# main.net
KiCad netlist of a schematic drawn in EAGLE
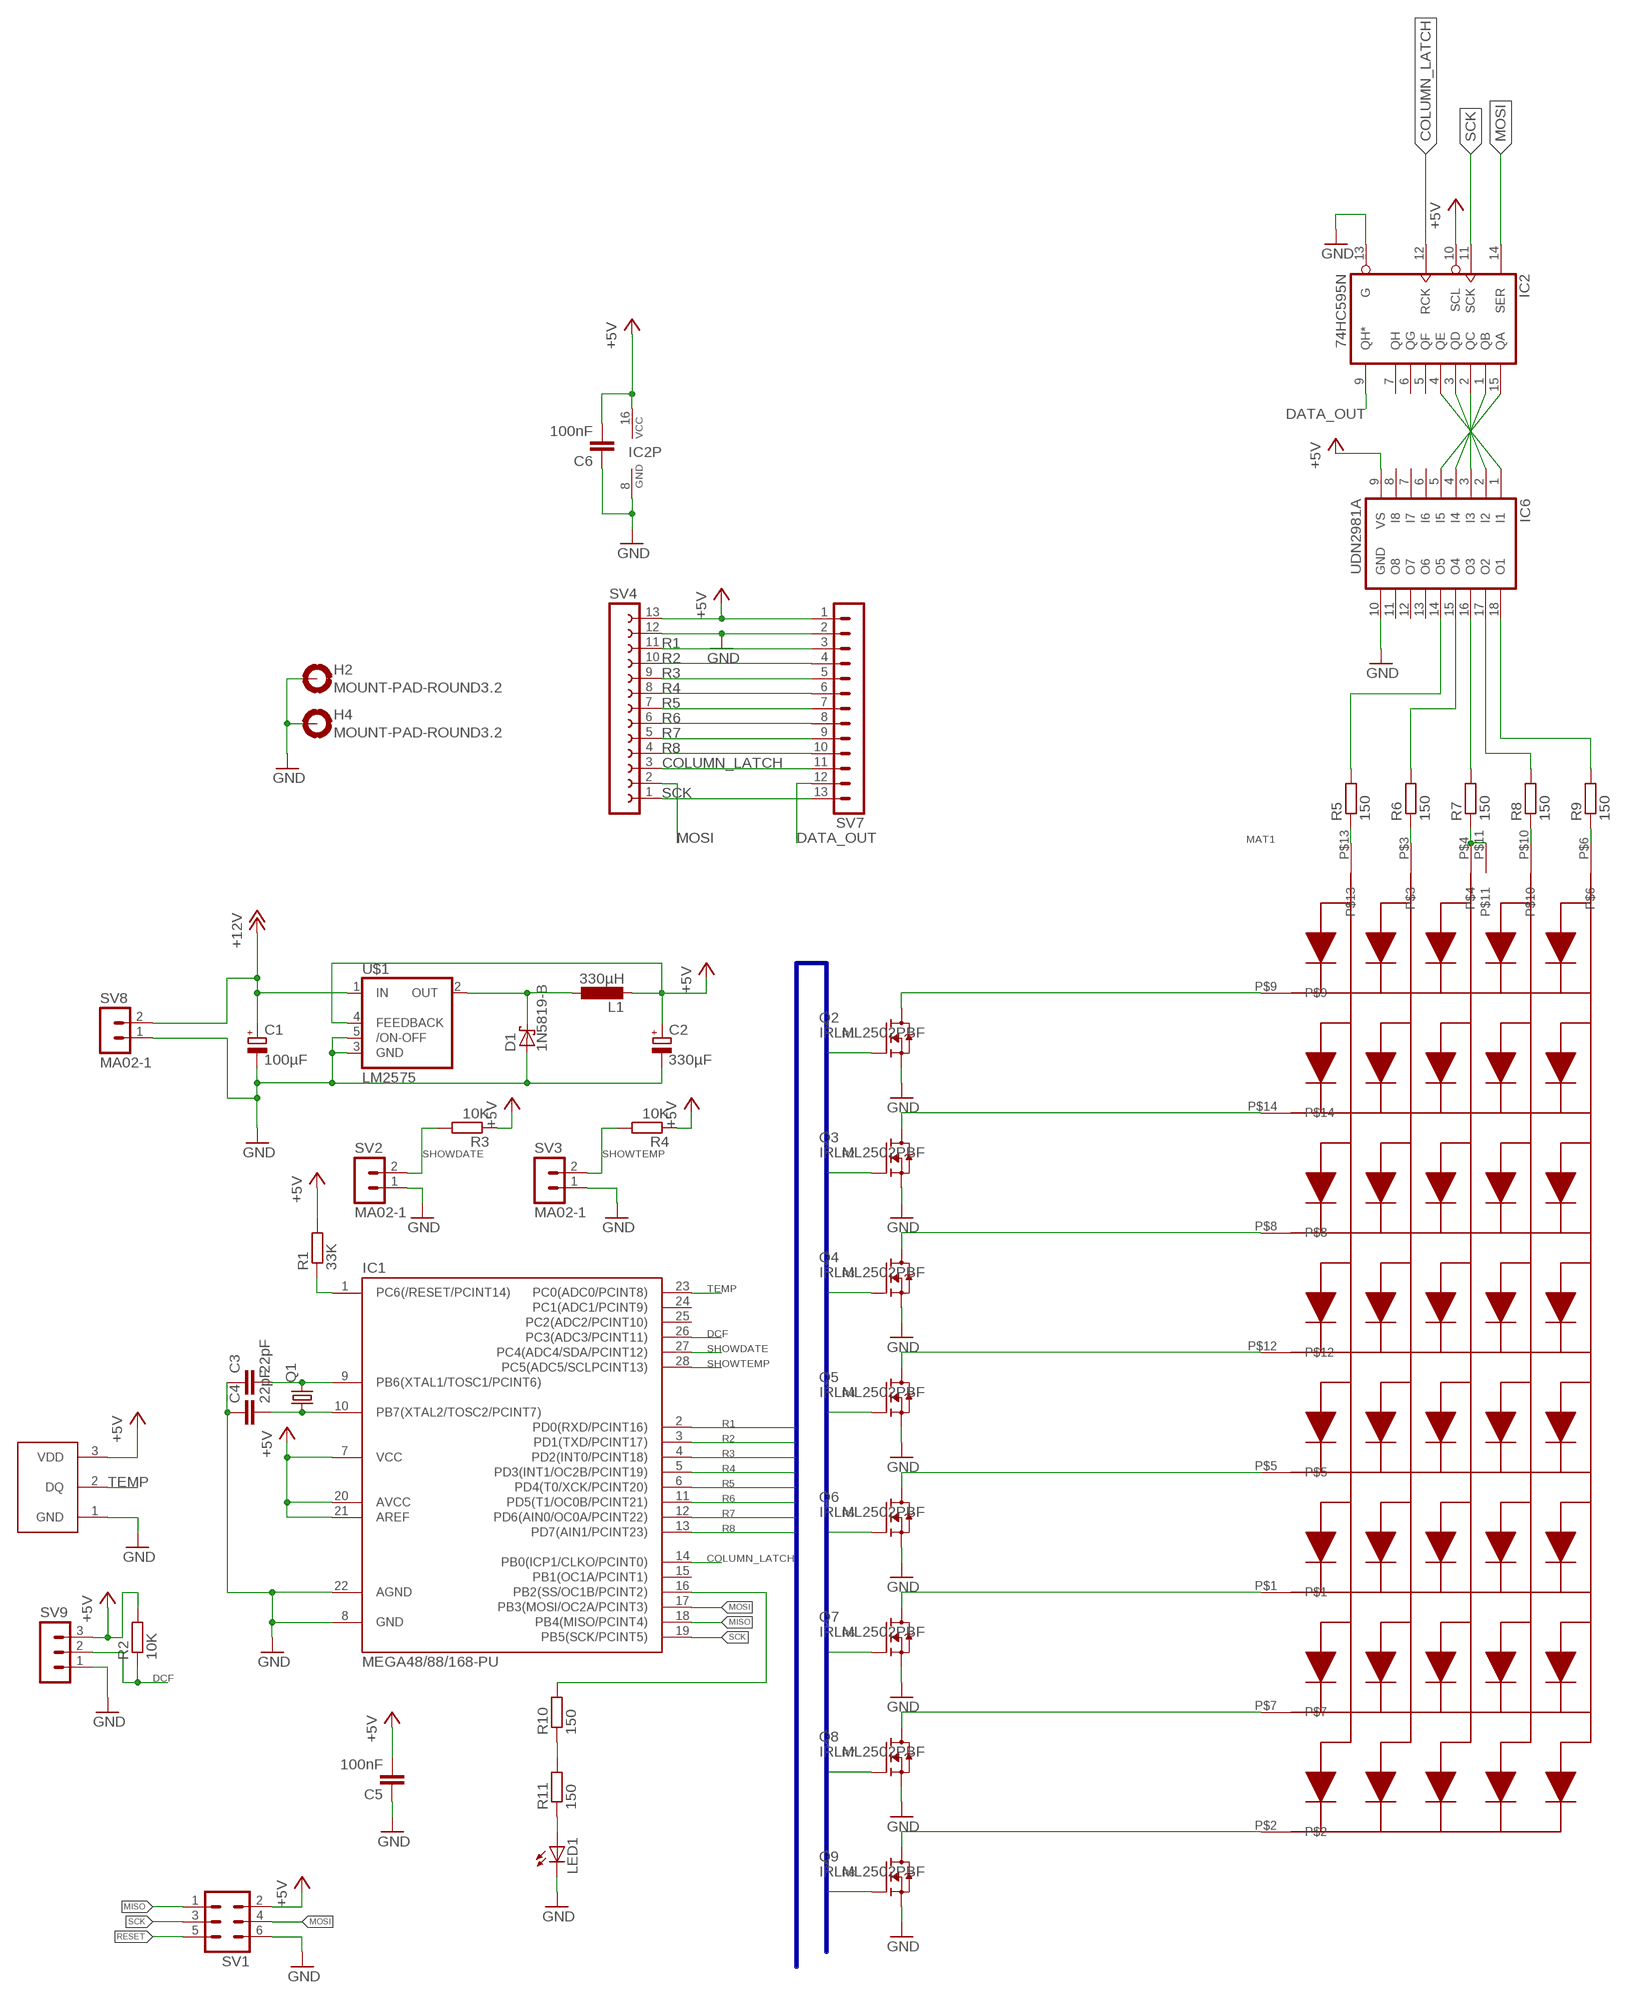
[diagram p0: schematic, sheet 1]

(export (version "E")
  (design (tool "Eeschema 10.0.6"))
  (components
    (comp (ref "C1")
      (value "100µF")
      (footprint "eagle-import:E2,5-5")
      (libsource (lib "eagle-import") (part "CPOL-EUE2.5-5"))
    )
    (comp (ref "C2")
      (value "330µF")
      (footprint "eagle-import:E3,5-8")
      (libsource (lib "eagle-import") (part "CPOL-EUE3.5-8"))
    )
    (comp (ref "C3")
      (value "22pF")
      (footprint "eagle-import:C025-025X050")
      (libsource (lib "eagle-import") (part "C-EU025-025X050"))
    )
    (comp (ref "C4")
      (value "22pF")
      (footprint "eagle-import:C025-025X050")
      (libsource (lib "eagle-import") (part "C-EU025-025X050"))
    )
    (comp (ref "C5")
      (value "100nF")
      (footprint "eagle-import:C0805")
      (libsource (lib "eagle-import") (part "C-EUC0805"))
    )
    (comp (ref "C6")
      (value "100nF")
      (footprint "eagle-import:C0805")
      (libsource (lib "eagle-import") (part "C-EUC0805"))
    )
    (comp (ref "D1")
      (value "1N5819-B")
      (footprint "eagle-import:DO41-7.6")
      (libsource (lib "eagle-import") (part "1N5819-B"))
    )
    (comp (ref "H2")
      (value "MOUNT-PAD-ROUND3.2")
      (footprint "eagle-import:3,2-PAD")
      (libsource (lib "eagle-import") (part "MOUNT-PAD-ROUND3.2"))
    )
    (comp (ref "H4")
      (value "MOUNT-PAD-ROUND3.2")
      (footprint "eagle-import:3,2-PAD")
      (libsource (lib "eagle-import") (part "MOUNT-PAD-ROUND3.2"))
    )
    (comp (ref "IC1")
      (value "MEGA48/88/168-PU")
      (footprint "eagle-import:DIL28-3")
      (libsource (lib "eagle-import") (part "MEGA48/88/168-PU"))
    )
    (comp (ref "IC2")
      (value "74HC595N")
      (footprint "eagle-import:DIL16")
      (libsource (lib "eagle-import") (part "74595NHC"))
    )
    (comp (ref "IC6")
      (value "UDN2981A")
      (footprint "eagle-import:DIL18")
      (libsource (lib "eagle-import") (part "UDN298A1"))
    )
    (comp (ref "L1")
      (value "330µH")
      (footprint "eagle-import:0204V")
      (libsource (lib "eagle-import") (part "L-EU0204V"))
    )
    (comp (ref "LED1")
      (value "LEDSML1206")
      (footprint "eagle-import:SML1206")
      (libsource (lib "eagle-import") (part "LEDSML1206"))
    )
    (comp (ref "MAT1")
      (value "5X8")
      (footprint "eagle-import:5X8")
      (libsource (lib "eagle-import") (part "5X8"))
    )
    (comp (ref "Q1")
      (value "CRYSTALHC49S")
      (footprint "eagle-import:HC49_S")
      (libsource (lib "eagle-import") (part "CRYSTALHC49S"))
    )
    (comp (ref "Q2")
      (value "IRLML2502PBF")
      (footprint "eagle-import:SOT23")
      (libsource (lib "eagle-import") (part "IRLML2502PBF"))
    )
    (comp (ref "Q3")
      (value "IRLML2502PBF")
      (footprint "eagle-import:SOT23")
      (libsource (lib "eagle-import") (part "IRLML2502PBF"))
    )
    (comp (ref "Q4")
      (value "IRLML2502PBF")
      (footprint "eagle-import:SOT23")
      (libsource (lib "eagle-import") (part "IRLML2502PBF"))
    )
    (comp (ref "Q5")
      (value "IRLML2502PBF")
      (footprint "eagle-import:SOT23")
      (libsource (lib "eagle-import") (part "IRLML2502PBF"))
    )
    (comp (ref "Q6")
      (value "IRLML2502PBF")
      (footprint "eagle-import:SOT23")
      (libsource (lib "eagle-import") (part "IRLML2502PBF"))
    )
    (comp (ref "Q7")
      (value "IRLML2502PBF")
      (footprint "eagle-import:SOT23")
      (libsource (lib "eagle-import") (part "IRLML2502PBF"))
    )
    (comp (ref "Q8")
      (value "IRLML2502PBF")
      (footprint "eagle-import:SOT23")
      (libsource (lib "eagle-import") (part "IRLML2502PBF"))
    )
    (comp (ref "Q9")
      (value "IRLML2502PBF")
      (footprint "eagle-import:SOT23")
      (libsource (lib "eagle-import") (part "IRLML2502PBF"))
    )
    (comp (ref "R1")
      (value "33K")
      (footprint "eagle-import:R0805")
      (libsource (lib "eagle-import") (part "R-EU_R0805"))
    )
    (comp (ref "R2")
      (value "10K")
      (footprint "eagle-import:R0805")
      (libsource (lib "eagle-import") (part "R-EU_R0805"))
    )
    (comp (ref "R3")
      (value "10K")
      (footprint "eagle-import:R0805")
      (libsource (lib "eagle-import") (part "R-EU_R0805"))
    )
    (comp (ref "R4")
      (value "10K")
      (footprint "eagle-import:R0805")
      (libsource (lib "eagle-import") (part "R-EU_R0805"))
    )
    (comp (ref "R5")
      (value "150")
      (footprint "eagle-import:R0805")
      (libsource (lib "eagle-import") (part "R-EU_R0805"))
    )
    (comp (ref "R6")
      (value "150")
      (footprint "eagle-import:R0805")
      (libsource (lib "eagle-import") (part "R-EU_R0805"))
    )
    (comp (ref "R7")
      (value "150")
      (footprint "eagle-import:R0805")
      (libsource (lib "eagle-import") (part "R-EU_R0805"))
    )
    (comp (ref "R8")
      (value "150")
      (footprint "eagle-import:R0805")
      (libsource (lib "eagle-import") (part "R-EU_R0805"))
    )
    (comp (ref "R9")
      (value "150")
      (footprint "eagle-import:R0805")
      (libsource (lib "eagle-import") (part "R-EU_R0805"))
    )
    (comp (ref "R10")
      (value "150")
      (footprint "eagle-import:R0805")
      (libsource (lib "eagle-import") (part "R-EU_R0805"))
    )
    (comp (ref "R11")
      (value "150")
      (footprint "eagle-import:R0805")
      (libsource (lib "eagle-import") (part "R-EU_R0805"))
    )
    (comp (ref "SV1")
      (value "MA03-2")
      (footprint "eagle-import:MA03-2")
      (libsource (lib "eagle-import") (part "MA03-2"))
    )
    (comp (ref "SV2")
      (value "MA02-1")
      (footprint "eagle-import:MA02-1")
      (libsource (lib "eagle-import") (part "MA02-1"))
    )
    (comp (ref "SV3")
      (value "MA02-1")
      (footprint "eagle-import:MA02-1")
      (libsource (lib "eagle-import") (part "MA02-1"))
    )
    (comp (ref "SV4")
      (value "FE13W")
      (footprint "eagle-import:FE13W")
      (libsource (lib "eagle-import") (part "FE13W"))
    )
    (comp (ref "SV7")
      (value "MA13-1W")
      (footprint "eagle-import:MA13-1W")
      (fields (field (name "OC_FARNELL") "unknown") (field (name "OC_NEWARK") "unknown"))
      (libsource (lib "eagle-import") (part "MA13-1W"))
    )
    (comp (ref "SV8")
      (value "MA02-1")
      (footprint "eagle-import:MA02-1")
      (libsource (lib "eagle-import") (part "MA02-1"))
    )
    (comp (ref "SV9")
      (value "MA03-1")
      (footprint "eagle-import:MA03-1")
      (libsource (lib "eagle-import") (part "MA03-1"))
    )
    (comp (ref "U$1")
      (value "LM2575")
      (footprint "eagle-import:LM2575")
      (libsource (lib "eagle-import") (part "LM2575"))
    )
    (comp (ref "U$2")
      (value "DS18B20")
      (footprint "eagle-import:TO92")
      (libsource (lib "eagle-import") (part "DS18B20"))
    )
  )
  (nets
    (net (code "1") (name "+5V") (class "Default")
      (node (ref "C2") (pin "+") (pinfunction "+_+") (pintype "passive"))
      (node (ref "C5") (pin "2") (pinfunction "2_2") (pintype "passive"))
      (node (ref "C6") (pin "2") (pinfunction "2_2") (pintype "passive"))
      (node (ref "IC1") (pin "20") (pinfunction "AVCC_20") (pintype "passive"))
      (node (ref "IC1") (pin "21") (pinfunction "AREF_21") (pintype "passive"))
      (node (ref "IC1") (pin "7") (pinfunction "VCC_7") (pintype "power_in"))
      (node (ref "IC2") (pin "10") (pinfunction "SCL_10") (pintype "input"))
      (node (ref "IC2") (pin "16") (pinfunction "VCC_16") (pintype "power_in"))
      (node (ref "IC6") (pin "9") (pinfunction "VS_9") (pintype "passive"))
      (node (ref "L1") (pin "2") (pinfunction "2_2") (pintype "passive"))
      (node (ref "R1") (pin "2") (pinfunction "2_2") (pintype "passive"))
      (node (ref "R2") (pin "2") (pinfunction "2_2") (pintype "passive"))
      (node (ref "R3") (pin "1") (pinfunction "1_1") (pintype "passive"))
      (node (ref "R4") (pin "1") (pinfunction "1_1") (pintype "passive"))
      (node (ref "SV1") (pin "2") (pinfunction "2_2") (pintype "passive"))
      (node (ref "SV4") (pin "13") (pinfunction "13_13") (pintype "passive"))
      (node (ref "SV7") (pin "1") (pinfunction "1_1") (pintype "passive"))
      (node (ref "SV9") (pin "3") (pinfunction "3_3") (pintype "passive"))
      (node (ref "U$1") (pin "4") (pinfunction "FEEDBACK_4") (pintype "input"))
      (node (ref "U$2") (pin "3") (pinfunction "VDD_3") (pintype "bidirectional"))
    )
    (net (code "2") (name "+12V") (class "Default")
      (node (ref "C1") (pin "+") (pinfunction "+_+") (pintype "passive"))
      (node (ref "SV8") (pin "2") (pinfunction "2_2") (pintype "passive"))
      (node (ref "U$1") (pin "1") (pinfunction "IN_1") (pintype "input"))
    )
    (net (code "3") (name "/DATA_OUT") (class "Default")
      (node (ref "IC2") (pin "9") (pinfunction "QH*_9") (pintype "tri_state"))
      (node (ref "SV7") (pin "12") (pinfunction "12_12") (pintype "passive"))
    )
    (net (code "4") (name "/DCF") (class "Default")
      (node (ref "IC1") (pin "26") (pinfunction "PC3(ADC3/PCINT11)_26") (pintype "bidirectional"))
      (node (ref "R2") (pin "1") (pinfunction "1_1") (pintype "passive"))
      (node (ref "SV9") (pin "2") (pinfunction "2_2") (pintype "passive"))
    )
    (net (code "5") (name "/R1") (class "Default")
      (node (ref "IC1") (pin "2") (pinfunction "PD0(RXD/PCINT16)_2") (pintype "bidirectional"))
      (node (ref "Q2") (pin "1") (pinfunction "G_1") (pintype "passive"))
      (node (ref "SV4") (pin "11") (pinfunction "11_11") (pintype "passive"))
      (node (ref "SV7") (pin "3") (pinfunction "3_3") (pintype "passive"))
    )
    (net (code "6") (name "/R2") (class "Default")
      (node (ref "IC1") (pin "3") (pinfunction "PD1(TXD/PCINT17)_3") (pintype "bidirectional"))
      (node (ref "Q3") (pin "1") (pinfunction "G_1") (pintype "passive"))
      (node (ref "SV4") (pin "10") (pinfunction "10_10") (pintype "passive"))
      (node (ref "SV7") (pin "4") (pinfunction "4_4") (pintype "passive"))
    )
    (net (code "7") (name "/R3") (class "Default")
      (node (ref "IC1") (pin "4") (pinfunction "PD2(INT0/PCINT18)_4") (pintype "bidirectional"))
      (node (ref "Q4") (pin "1") (pinfunction "G_1") (pintype "passive"))
      (node (ref "SV4") (pin "9") (pinfunction "9_9") (pintype "passive"))
      (node (ref "SV7") (pin "5") (pinfunction "5_5") (pintype "passive"))
    )
    (net (code "8") (name "/R4") (class "Default")
      (node (ref "IC1") (pin "5") (pinfunction "PD3(INT1/OC2B/PCINT19)_5") (pintype "bidirectional"))
      (node (ref "Q5") (pin "1") (pinfunction "G_1") (pintype "passive"))
      (node (ref "SV4") (pin "8") (pinfunction "8_8") (pintype "passive"))
      (node (ref "SV7") (pin "6") (pinfunction "6_6") (pintype "passive"))
    )
    (net (code "9") (name "/R5") (class "Default")
      (node (ref "IC1") (pin "6") (pinfunction "PD4(T0/XCK/PCINT20)_6") (pintype "bidirectional"))
      (node (ref "Q6") (pin "1") (pinfunction "G_1") (pintype "passive"))
      (node (ref "SV4") (pin "7") (pinfunction "7_7") (pintype "passive"))
      (node (ref "SV7") (pin "7") (pinfunction "7_7") (pintype "passive"))
    )
    (net (code "10") (name "/R6") (class "Default")
      (node (ref "IC1") (pin "11") (pinfunction "PD5(T1/OC0B/PCINT21)_11") (pintype "bidirectional"))
      (node (ref "Q7") (pin "1") (pinfunction "G_1") (pintype "passive"))
      (node (ref "SV4") (pin "6") (pinfunction "6_6") (pintype "passive"))
      (node (ref "SV7") (pin "8") (pinfunction "8_8") (pintype "passive"))
    )
    (net (code "11") (name "/R7") (class "Default")
      (node (ref "IC1") (pin "12") (pinfunction "PD6(AIN0/OC0A/PCINT22)_12") (pintype "bidirectional"))
      (node (ref "Q8") (pin "1") (pinfunction "G_1") (pintype "passive"))
      (node (ref "SV4") (pin "5") (pinfunction "5_5") (pintype "passive"))
      (node (ref "SV7") (pin "9") (pinfunction "9_9") (pintype "passive"))
    )
    (net (code "12") (name "/R8") (class "Default")
      (node (ref "IC1") (pin "13") (pinfunction "PD7(AIN1/PCINT23)_13") (pintype "bidirectional"))
      (node (ref "Q9") (pin "1") (pinfunction "G_1") (pintype "passive"))
      (node (ref "SV4") (pin "4") (pinfunction "4_4") (pintype "passive"))
      (node (ref "SV7") (pin "10") (pinfunction "10_10") (pintype "passive"))
    )
    (net (code "13") (name "/SHOWDATE") (class "Default")
      (node (ref "IC1") (pin "27") (pinfunction "PC4(ADC4/SDA/PCINT12)_27") (pintype "bidirectional"))
      (node (ref "R3") (pin "2") (pinfunction "2_2") (pintype "passive"))
      (node (ref "SV2") (pin "2") (pinfunction "2_2") (pintype "passive"))
    )
    (net (code "14") (name "/SHOWTEMP") (class "Default")
      (node (ref "IC1") (pin "28") (pinfunction "PC5(ADC5/SCLPCINT13)_28") (pintype "bidirectional"))
      (node (ref "R4") (pin "2") (pinfunction "2_2") (pintype "passive"))
      (node (ref "SV3") (pin "2") (pinfunction "2_2") (pintype "passive"))
    )
    (net (code "15") (name "/TEMP") (class "Default")
      (node (ref "IC1") (pin "23") (pinfunction "PC0(ADC0/PCINT8)_23") (pintype "bidirectional"))
      (node (ref "U$2") (pin "2") (pinfunction "DQ_2") (pintype "bidirectional"))
    )
    (net (code "16") (name "COLUMN_LATCH") (class "Default")
      (node (ref "IC1") (pin "14") (pinfunction "PB0(ICP1/CLKO/PCINT0)_14") (pintype "bidirectional"))
      (node (ref "IC2") (pin "12") (pinfunction "RCK_12") (pintype "input"))
      (node (ref "SV4") (pin "3") (pinfunction "3_3") (pintype "passive"))
      (node (ref "SV7") (pin "11") (pinfunction "11_11") (pintype "passive"))
    )
    (net (code "17") (name "GND") (class "Default")
      (node (ref "C1") (pin "-") (pinfunction "-_-") (pintype "passive"))
      (node (ref "C2") (pin "-") (pinfunction "-_-") (pintype "passive"))
      (node (ref "C3") (pin "1") (pinfunction "1_1") (pintype "passive"))
      (node (ref "C4") (pin "1") (pinfunction "1_1") (pintype "passive"))
      (node (ref "C5") (pin "1") (pinfunction "1_1") (pintype "passive"))
      (node (ref "C6") (pin "1") (pinfunction "1_1") (pintype "passive"))
      (node (ref "D1") (pin "A") (pinfunction "A_A") (pintype "passive"))
      (node (ref "H2") (pin "B3,2") (pinfunction "MOUNT_B3,2") (pintype "passive"))
      (node (ref "H4") (pin "B3,2") (pinfunction "MOUNT_B3,2") (pintype "passive"))
      (node (ref "IC1") (pin "22") (pinfunction "AGND_22") (pintype "power_in"))
      (node (ref "IC1") (pin "8") (pinfunction "GND_8") (pintype "power_in"))
      (node (ref "IC2") (pin "13") (pinfunction "G_13") (pintype "input"))
      (node (ref "IC2") (pin "8") (pinfunction "GND_8") (pintype "power_in"))
      (node (ref "IC6") (pin "10") (pinfunction "GND_10") (pintype "power_in"))
      (node (ref "LED1") (pin "C") (pinfunction "C_C") (pintype "passive"))
      (node (ref "Q2") (pin "2") (pinfunction "S_2") (pintype "passive"))
      (node (ref "Q3") (pin "2") (pinfunction "S_2") (pintype "passive"))
      (node (ref "Q4") (pin "2") (pinfunction "S_2") (pintype "passive"))
      (node (ref "Q5") (pin "2") (pinfunction "S_2") (pintype "passive"))
      (node (ref "Q6") (pin "2") (pinfunction "S_2") (pintype "passive"))
      (node (ref "Q7") (pin "2") (pinfunction "S_2") (pintype "passive"))
      (node (ref "Q8") (pin "2") (pinfunction "S_2") (pintype "passive"))
      (node (ref "Q9") (pin "2") (pinfunction "S_2") (pintype "passive"))
      (node (ref "SV1") (pin "6") (pinfunction "6_6") (pintype "passive"))
      (node (ref "SV2") (pin "1") (pinfunction "1_1") (pintype "passive"))
      (node (ref "SV3") (pin "1") (pinfunction "1_1") (pintype "passive"))
      (node (ref "SV4") (pin "12") (pinfunction "12_12") (pintype "passive"))
      (node (ref "SV7") (pin "2") (pinfunction "2_2") (pintype "passive"))
      (node (ref "SV8") (pin "1") (pinfunction "1_1") (pintype "passive"))
      (node (ref "SV9") (pin "1") (pinfunction "1_1") (pintype "passive"))
      (node (ref "U$1") (pin "3") (pinfunction "GND_3") (pintype "passive"))
      (node (ref "U$1") (pin "5") (pinfunction "/ON-OFF_5") (pintype "input"))
      (node (ref "U$2") (pin "1") (pinfunction "GND_1") (pintype "bidirectional"))
    )
    (net (code "18") (name "MISO") (class "Default")
      (node (ref "IC1") (pin "18") (pinfunction "PB4(MISO/PCINT4)_18") (pintype "bidirectional"))
      (node (ref "SV1") (pin "1") (pinfunction "1_1") (pintype "passive"))
    )
    (net (code "19") (name "MOSI") (class "Default")
      (node (ref "IC1") (pin "17") (pinfunction "PB3(MOSI/OC2A/PCINT3)_17") (pintype "bidirectional"))
      (node (ref "IC2") (pin "14") (pinfunction "SER_14") (pintype "input"))
      (node (ref "SV1") (pin "4") (pinfunction "4_4") (pintype "passive"))
      (node (ref "SV4") (pin "2") (pinfunction "2_2") (pintype "passive"))
    )
    (net (code "20") (name "Net-(IC1-PB2(SS{slash}OC1B{slash}PCINT2))") (class "Default")
      (node (ref "IC1") (pin "16") (pinfunction "PB2(SS/OC1B/PCINT2)_16") (pintype "bidirectional"))
      (node (ref "R10") (pin "2") (pinfunction "2_2") (pintype "passive"))
    )
    (net (code "21") (name "Net-(IC1-PB6(XTAL1{slash}TOSC1{slash}PCINT6))") (class "Default")
      (node (ref "C3") (pin "2") (pinfunction "2_2") (pintype "passive"))
      (node (ref "IC1") (pin "9") (pinfunction "PB6(XTAL1/TOSC1/PCINT6)_9") (pintype "bidirectional"))
      (node (ref "Q1") (pin "2") (pinfunction "2_2") (pintype "passive"))
    )
    (net (code "22") (name "Net-(IC1-PB7(XTAL2{slash}TOSC2{slash}PCINT7))") (class "Default")
      (node (ref "C4") (pin "2") (pinfunction "2_2") (pintype "passive"))
      (node (ref "IC1") (pin "10") (pinfunction "PB7(XTAL2/TOSC2/PCINT7)_10") (pintype "bidirectional"))
      (node (ref "Q1") (pin "1") (pinfunction "1_1") (pintype "passive"))
    )
    (net (code "23") (name "Net-(IC2A-QA)") (class "Default")
      (node (ref "IC2") (pin "15") (pinfunction "QA_15") (pintype "tri_state"))
      (node (ref "IC6") (pin "5") (pinfunction "I5_5") (pintype "input"))
    )
    (net (code "24") (name "Net-(IC2A-QB)") (class "Default")
      (node (ref "IC2") (pin "1") (pinfunction "QB_1") (pintype "tri_state"))
      (node (ref "IC6") (pin "4") (pinfunction "I4_4") (pintype "input"))
    )
    (net (code "25") (name "Net-(IC2A-QC)") (class "Default")
      (node (ref "IC2") (pin "2") (pinfunction "QC_2") (pintype "tri_state"))
      (node (ref "IC6") (pin "3") (pinfunction "I3_3") (pintype "input"))
    )
    (net (code "26") (name "Net-(IC2A-QD)") (class "Default")
      (node (ref "IC2") (pin "3") (pinfunction "QD_3") (pintype "tri_state"))
      (node (ref "IC6") (pin "2") (pinfunction "I2_2") (pintype "input"))
    )
    (net (code "27") (name "Net-(IC2A-QE)") (class "Default")
      (node (ref "IC2") (pin "4") (pinfunction "QE_4") (pintype "tri_state"))
      (node (ref "IC6") (pin "1") (pinfunction "I1_1") (pintype "input"))
    )
    (net (code "28") (name "Net-(IC6-O1)") (class "Default")
      (node (ref "IC6") (pin "18") (pinfunction "O1_18") (pintype "open_collector"))
      (node (ref "R9") (pin "2") (pinfunction "2_2") (pintype "passive"))
    )
    (net (code "29") (name "Net-(IC6-O2)") (class "Default")
      (node (ref "IC6") (pin "17") (pinfunction "O2_17") (pintype "open_collector"))
      (node (ref "R8") (pin "2") (pinfunction "2_2") (pintype "passive"))
    )
    (net (code "30") (name "Net-(IC6-O3)") (class "Default")
      (node (ref "IC6") (pin "16") (pinfunction "O3_16") (pintype "open_collector"))
      (node (ref "R7") (pin "2") (pinfunction "2_2") (pintype "passive"))
    )
    (net (code "31") (name "Net-(IC6-O4)") (class "Default")
      (node (ref "IC6") (pin "15") (pinfunction "O4_15") (pintype "open_collector"))
      (node (ref "R6") (pin "2") (pinfunction "2_2") (pintype "passive"))
    )
    (net (code "32") (name "Net-(IC6-O5)") (class "Default")
      (node (ref "IC6") (pin "14") (pinfunction "O5_14") (pintype "open_collector"))
      (node (ref "R5") (pin "2") (pinfunction "2_2") (pintype "passive"))
    )
    (net (code "33") (name "Net-(LED1-PadA)") (class "Default")
      (node (ref "LED1") (pin "A") (pinfunction "A_A") (pintype "passive"))
      (node (ref "R11") (pin "1") (pinfunction "1_1") (pintype "passive"))
    )
    (net (code "34") (name "Net-(MAT1-PadP$3)") (class "Default")
      (node (ref "MAT1") (pin "P$3") (pinfunction "P$3_P$3") (pintype "bidirectional"))
      (node (ref "R6") (pin "1") (pinfunction "1_1") (pintype "passive"))
    )
    (net (code "35") (name "Net-(MAT1-PadP$6)") (class "Default")
      (node (ref "MAT1") (pin "P$6") (pinfunction "P$6_P$6") (pintype "bidirectional"))
      (node (ref "R9") (pin "1") (pinfunction "1_1") (pintype "passive"))
    )
    (net (code "36") (name "Net-(MAT1-PadP$10)") (class "Default")
      (node (ref "MAT1") (pin "P$10") (pinfunction "P$10_P$10") (pintype "bidirectional"))
      (node (ref "R8") (pin "1") (pinfunction "1_1") (pintype "passive"))
    )
    (net (code "37") (name "Net-(MAT1-PadP$11)") (class "Default")
      (node (ref "MAT1") (pin "P$11") (pinfunction "P$11_P$11") (pintype "bidirectional"))
      (node (ref "MAT1") (pin "P$4") (pinfunction "P$4_P$4") (pintype "bidirectional"))
      (node (ref "R7") (pin "1") (pinfunction "1_1") (pintype "passive"))
    )
    (net (code "38") (name "Net-(MAT1-PadP$13)") (class "Default")
      (node (ref "MAT1") (pin "P$13") (pinfunction "P$13_P$13") (pintype "bidirectional"))
      (node (ref "R5") (pin "1") (pinfunction "1_1") (pintype "passive"))
    )
    (net (code "39") (name "Net-(Q2-D)") (class "Default")
      (node (ref "MAT1") (pin "P$9") (pinfunction "P$9_P$9") (pintype "bidirectional"))
      (node (ref "Q2") (pin "3") (pinfunction "D_3") (pintype "passive"))
    )
    (net (code "40") (name "Net-(Q3-D)") (class "Default")
      (node (ref "MAT1") (pin "P$14") (pinfunction "P$14_P$14") (pintype "bidirectional"))
      (node (ref "Q3") (pin "3") (pinfunction "D_3") (pintype "passive"))
    )
    (net (code "41") (name "Net-(Q4-D)") (class "Default")
      (node (ref "MAT1") (pin "P$8") (pinfunction "P$8_P$8") (pintype "bidirectional"))
      (node (ref "Q4") (pin "3") (pinfunction "D_3") (pintype "passive"))
    )
    (net (code "42") (name "Net-(Q5-D)") (class "Default")
      (node (ref "MAT1") (pin "P$12") (pinfunction "P$12_P$12") (pintype "bidirectional"))
      (node (ref "Q5") (pin "3") (pinfunction "D_3") (pintype "passive"))
    )
    (net (code "43") (name "Net-(Q6-D)") (class "Default")
      (node (ref "MAT1") (pin "P$5") (pinfunction "P$5_P$5") (pintype "bidirectional"))
      (node (ref "Q6") (pin "3") (pinfunction "D_3") (pintype "passive"))
    )
    (net (code "44") (name "Net-(Q7-D)") (class "Default")
      (node (ref "MAT1") (pin "P$1") (pinfunction "P$1_P$1") (pintype "bidirectional"))
      (node (ref "Q7") (pin "3") (pinfunction "D_3") (pintype "passive"))
    )
    (net (code "45") (name "Net-(Q8-D)") (class "Default")
      (node (ref "MAT1") (pin "P$7") (pinfunction "P$7_P$7") (pintype "bidirectional"))
      (node (ref "Q8") (pin "3") (pinfunction "D_3") (pintype "passive"))
    )
    (net (code "46") (name "Net-(Q9-D)") (class "Default")
      (node (ref "MAT1") (pin "P$2") (pinfunction "P$2_P$2") (pintype "bidirectional"))
      (node (ref "Q9") (pin "3") (pinfunction "D_3") (pintype "passive"))
    )
    (net (code "47") (name "Net-(R10-Pad1)") (class "Default")
      (node (ref "R10") (pin "1") (pinfunction "1_1") (pintype "passive"))
      (node (ref "R11") (pin "2") (pinfunction "2_2") (pintype "passive"))
    )
    (net (code "48") (name "Net-(U$1-OUT)") (class "Default")
      (node (ref "D1") (pin "C") (pinfunction "C_C") (pintype "passive"))
      (node (ref "L1") (pin "1") (pinfunction "1_1") (pintype "passive"))
      (node (ref "U$1") (pin "2") (pinfunction "OUT_2") (pintype "passive"))
    )
    (net (code "49") (name "RESET") (class "Default")
      (node (ref "IC1") (pin "1") (pinfunction "PC6(/RESET/PCINT14)_1") (pintype "bidirectional"))
      (node (ref "R1") (pin "1") (pinfunction "1_1") (pintype "passive"))
      (node (ref "SV1") (pin "5") (pinfunction "5_5") (pintype "passive"))
    )
    (net (code "50") (name "SCK") (class "Default")
      (node (ref "IC1") (pin "19") (pinfunction "PB5(SCK/PCINT5)_19") (pintype "bidirectional"))
      (node (ref "IC2") (pin "11") (pinfunction "SCK_11") (pintype "input"))
      (node (ref "SV1") (pin "3") (pinfunction "3_3") (pintype "passive"))
      (node (ref "SV4") (pin "1") (pinfunction "1_1") (pintype "passive"))
      (node (ref "SV7") (pin "13") (pinfunction "13_13") (pintype "passive"))
    )
    (net (code "51") (name "unconnected-(IC1-PB1(OC1A{slash}PCINT1)-Pad15)") (class "Default")
      (node (ref "IC1") (pin "15") (pinfunction "PB1(OC1A/PCINT1)_15") (pintype "bidirectional"))
    )
    (net (code "52") (name "unconnected-(IC1-PC1(ADC1{slash}PCINT9)-Pad24)") (class "Default")
      (node (ref "IC1") (pin "24") (pinfunction "PC1(ADC1/PCINT9)_24") (pintype "bidirectional"))
    )
    (net (code "53") (name "unconnected-(IC1-PC2(ADC2{slash}PCINT10)-Pad25)") (class "Default")
      (node (ref "IC1") (pin "25") (pinfunction "PC2(ADC2/PCINT10)_25") (pintype "bidirectional"))
    )
    (net (code "54") (name "unconnected-(IC2A-QF-Pad5)") (class "Default")
      (node (ref "IC2") (pin "5") (pinfunction "QF_5") (pintype "tri_state"))
    )
    (net (code "55") (name "unconnected-(IC2A-QG-Pad6)") (class "Default")
      (node (ref "IC2") (pin "6") (pinfunction "QG_6") (pintype "tri_state"))
    )
    (net (code "56") (name "unconnected-(IC2A-QH-Pad7)") (class "Default")
      (node (ref "IC2") (pin "7") (pinfunction "QH_7") (pintype "tri_state"))
    )
    (net (code "57") (name "unconnected-(IC6-I6-Pad6)") (class "Default")
      (node (ref "IC6") (pin "6") (pinfunction "I6_6") (pintype "input"))
    )
    (net (code "58") (name "unconnected-(IC6-I7-Pad7)") (class "Default")
      (node (ref "IC6") (pin "7") (pinfunction "I7_7") (pintype "input"))
    )
    (net (code "59") (name "unconnected-(IC6-I8-Pad8)") (class "Default")
      (node (ref "IC6") (pin "8") (pinfunction "I8_8") (pintype "input"))
    )
    (net (code "60") (name "unconnected-(IC6-O6-Pad13)") (class "Default")
      (node (ref "IC6") (pin "13") (pinfunction "O6_13") (pintype "open_collector"))
    )
    (net (code "61") (name "unconnected-(IC6-O7-Pad12)") (class "Default")
      (node (ref "IC6") (pin "12") (pinfunction "O7_12") (pintype "open_collector"))
    )
    (net (code "62") (name "unconnected-(IC6-O8-Pad11)") (class "Default")
      (node (ref "IC6") (pin "11") (pinfunction "O8_11") (pintype "open_collector"))
    )
  )
)
